# Connectors.net
KiCad netlist of a schematic drawn in Altium Designer
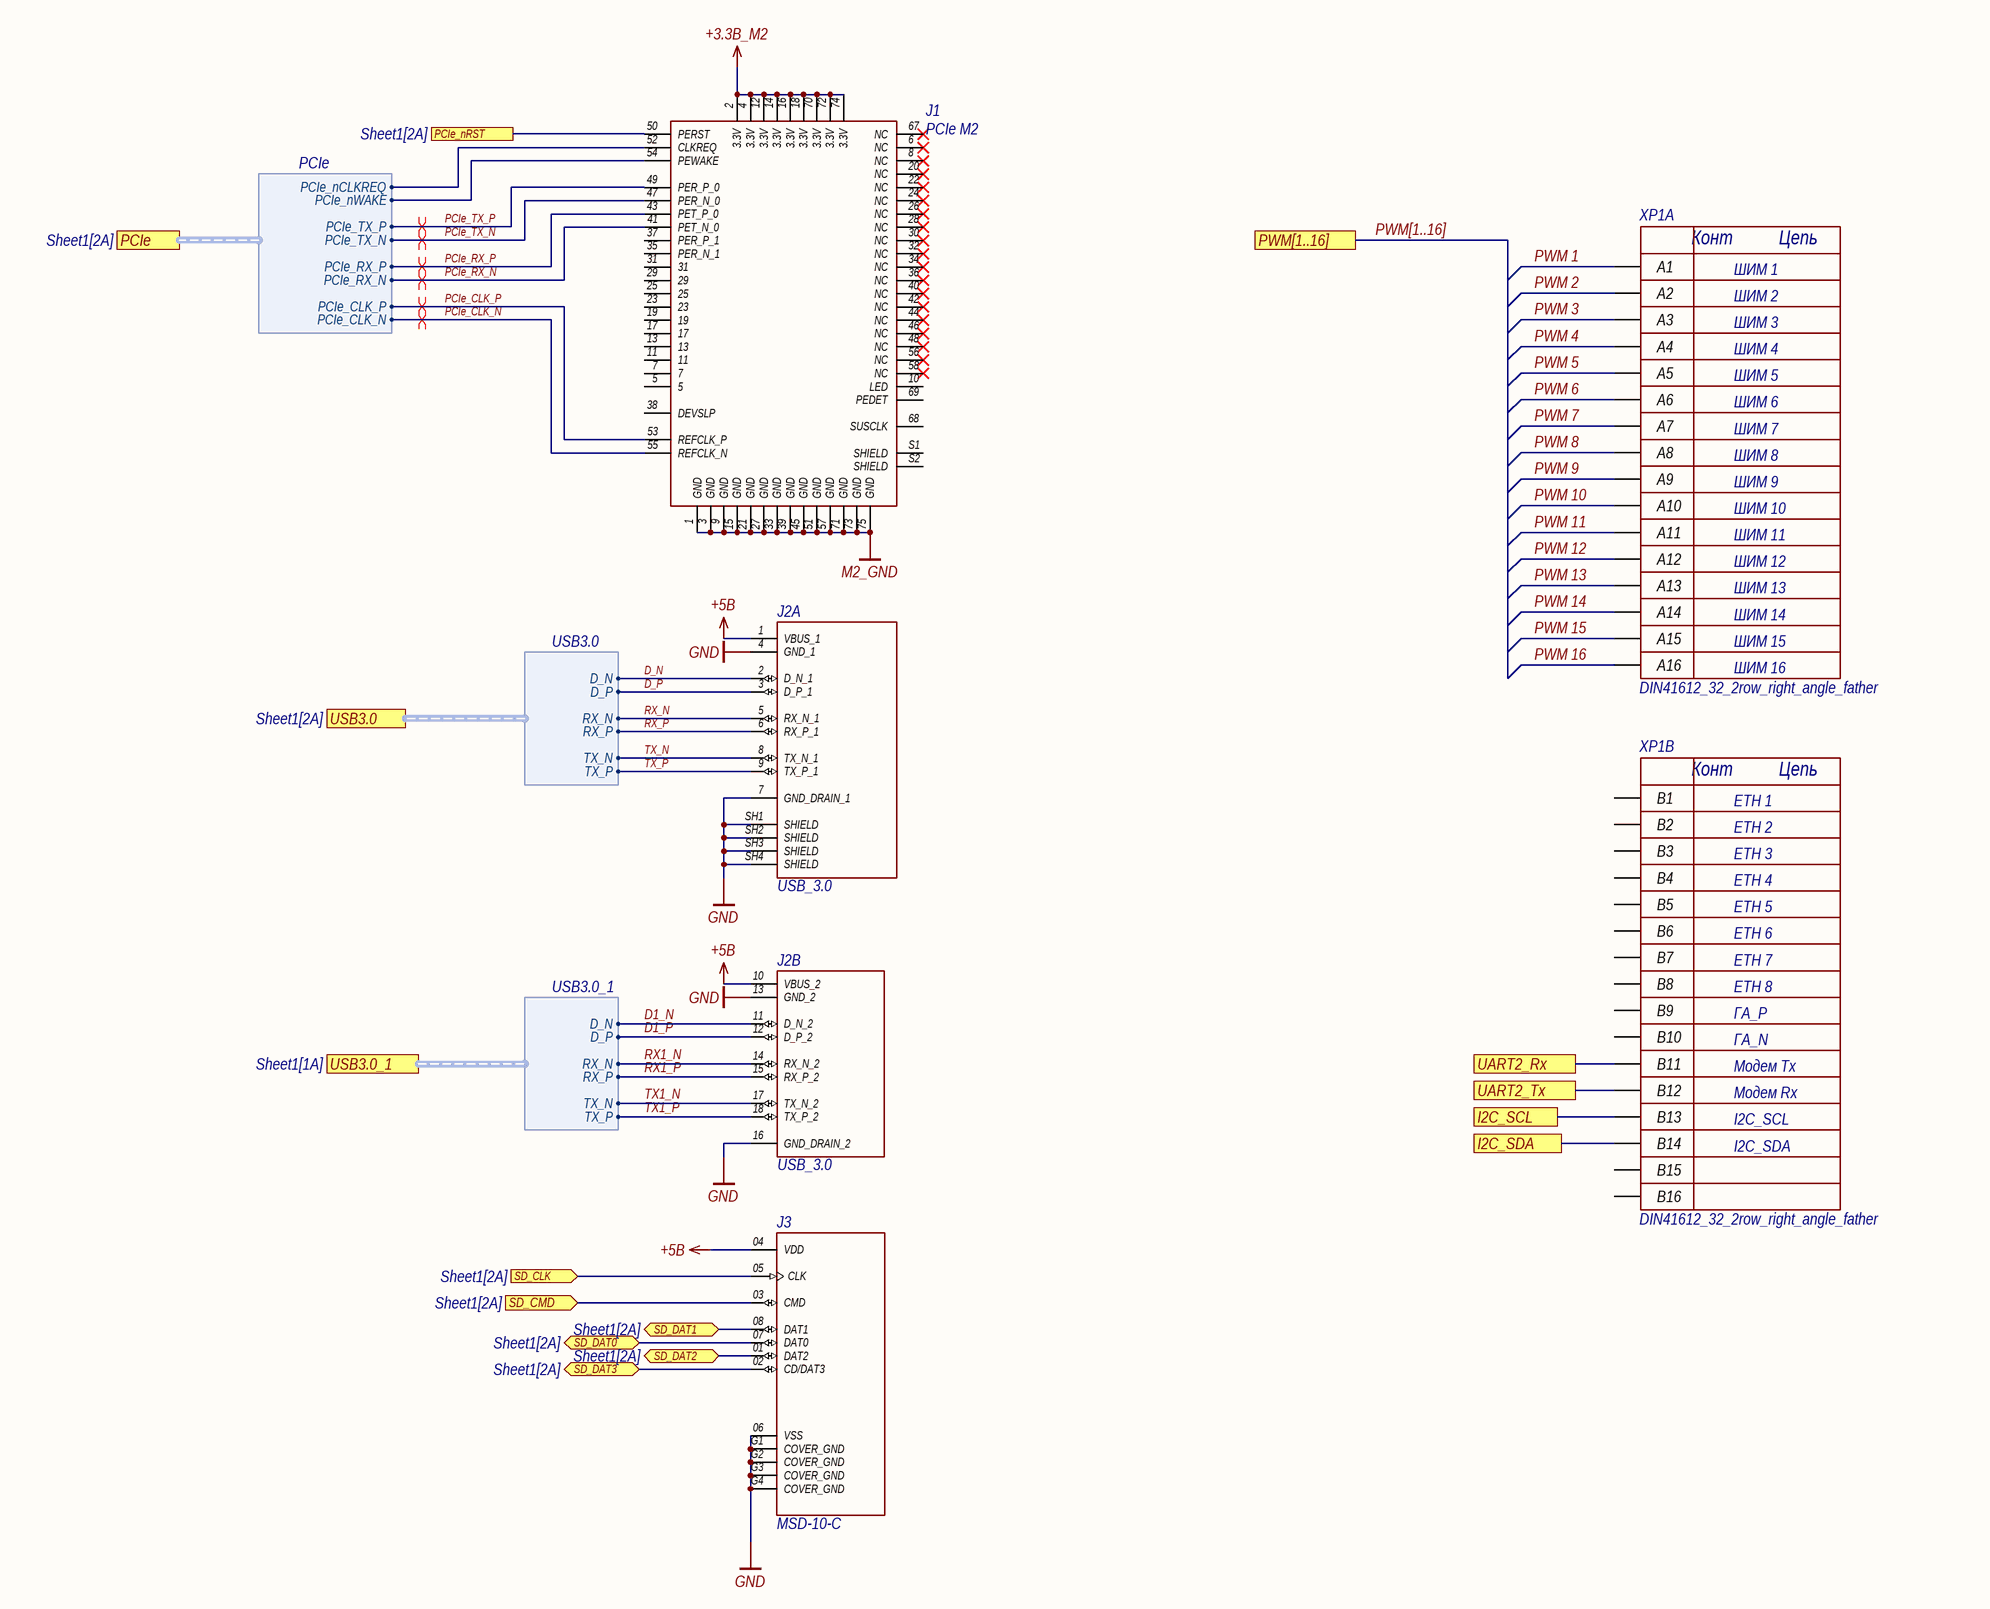
[diagram p0: Connectors.SchDoc]

(export (version "E")
  (design (tool "Eeschema 10.0.6"))
  (components
    (comp (ref "J1")
      (value "PCIe M2")
      (footprint "PCIe M2")
      (description "PCIe M.2 Connectors, Storage and Server Connector, P=0.5mm, H=3.2mm, Key M,Gold Plating")
      (fields (field (name "MF") "Amphenol") (field (name "MP") "MDT320M03001"))
      (libsource (lib "Hydrolib") (part "PCIe M2"))
    )
    (comp (ref "J2")
      (value "USB_3.0")
      (footprint "USB_3.0")
      (description "Двойной USB 3.0")
      (fields (field (name "MF") "Stewart Connector") (field (name "MP") "SS-52000-003"))
      (libsource (lib "Hydrolib") (part "USB_3.0"))
    )
    (comp (ref "J3")
      (value "MSD-10-C")
      (footprint "CUI_MSD-10-C")
      (fields (field (name "MF") "Same Sky"))
      (libsource (lib "Hydrolib") (part "MSD-10-C"))
    )
    (comp (ref "XP1")
      (value "DIN41612_32_2row_right_angle_father")
      (footprint "DIN41612_32_2row_right_angle_father")
      (libsource (lib "Hydrolib") (part "DIN41612_32_2row"))
    )
  )
  (nets
    (net (code "20") (name "+3.3В_M2") (class "Default")
      (node (ref "J1") (pin "12") (pinfunction "3.3V_12") (pintype "passive"))
      (node (ref "J1") (pin "14") (pinfunction "3.3V_14") (pintype "passive"))
      (node (ref "J1") (pin "16") (pinfunction "3.3V_16") (pintype "passive"))
      (node (ref "J1") (pin "18") (pinfunction "3.3V_18") (pintype "passive"))
      (node (ref "J1") (pin "2") (pinfunction "3.3V_2") (pintype "passive"))
      (node (ref "J1") (pin "4") (pinfunction "3.3V_4") (pintype "passive"))
      (node (ref "J1") (pin "70") (pinfunction "3.3V_70") (pintype "passive"))
      (node (ref "J1") (pin "72") (pinfunction "3.3V_72") (pintype "passive"))
      (node (ref "J1") (pin "74") (pinfunction "3.3V_74") (pintype "passive"))
    )
    (net (code "21") (name "+5В") (class "Default")
      (node (ref "J2") (pin "1") (pinfunction "VBUS_1_1") (pintype "power_in"))
      (node (ref "J2") (pin "10") (pinfunction "VBUS_2_10") (pintype "power_in"))
      (node (ref "J3") (pin "04") (pinfunction "VDD_04") (pintype "power_in"))
    )
    (net (code "22") (name "/D1_N") (class "Default")
      (node (ref "J2") (pin "11") (pinfunction "D_N_2_11") (pintype "bidirectional"))
    )
    (net (code "23") (name "/D1_P") (class "Default")
      (node (ref "J2") (pin "12") (pinfunction "D_P_2_12") (pintype "bidirectional"))
    )
    (net (code "24") (name "/D_N") (class "Default")
      (node (ref "J2") (pin "2") (pinfunction "D_N_1_2") (pintype "bidirectional"))
    )
    (net (code "25") (name "/D_P") (class "Default")
      (node (ref "J2") (pin "3") (pinfunction "D_P_1_3") (pintype "bidirectional"))
    )
    (net (code "26") (name "/I2C_SCL") (class "Default")
      (node (ref "XP1") (pin "B13") (pinfunction "B13_B13") (pintype "passive"))
    )
    (net (code "27") (name "/I2C_SDA") (class "Default")
      (node (ref "XP1") (pin "B14") (pinfunction "B14_B14") (pintype "passive"))
    )
    (net (code "28") (name "/PCIe_CLK_N") (class "Default")
      (node (ref "J1") (pin "55") (pinfunction "REFCLK_N_55") (pintype "passive"))
    )
    (net (code "29") (name "/PCIe_CLK_P") (class "Default")
      (node (ref "J1") (pin "53") (pinfunction "REFCLK_P_53") (pintype "passive"))
    )
    (net (code "30") (name "/PCIe_RX_N") (class "Default")
      (node (ref "J1") (pin "41") (pinfunction "PET_N_0_41") (pintype "passive"))
    )
    (net (code "31") (name "/PCIe_RX_P") (class "Default")
      (node (ref "J1") (pin "43") (pinfunction "PET_P_0_43") (pintype "passive"))
    )
    (net (code "32") (name "/PCIe_TX_N") (class "Default")
      (node (ref "J1") (pin "47") (pinfunction "PER_N_0_47") (pintype "passive"))
    )
    (net (code "33") (name "/PCIe_TX_P") (class "Default")
      (node (ref "J1") (pin "49") (pinfunction "PER_P_0_49") (pintype "passive"))
    )
    (net (code "34") (name "/PCIe_nCLKREQ") (class "Default")
      (node (ref "J1") (pin "52") (pinfunction "CLKREQ_52") (pintype "passive"))
    )
    (net (code "35") (name "/PCIe_nRST") (class "Default")
      (node (ref "J1") (pin "50") (pinfunction "PERST_50") (pintype "passive"))
    )
    (net (code "36") (name "/PCIe_nWAKE") (class "Default")
      (node (ref "J1") (pin "54") (pinfunction "PEWAKE_54") (pintype "passive"))
    )
    (net (code "37") (name "/PWM 1") (class "Default")
      (node (ref "XP1") (pin "A1") (pinfunction "A1_A1") (pintype "passive"))
    )
    (net (code "38") (name "/PWM 2") (class "Default")
      (node (ref "XP1") (pin "A2") (pinfunction "A2_A2") (pintype "passive"))
    )
    (net (code "39") (name "/PWM 3") (class "Default")
      (node (ref "XP1") (pin "A3") (pinfunction "A3_A3") (pintype "passive"))
    )
    (net (code "40") (name "/PWM 4") (class "Default")
      (node (ref "XP1") (pin "A4") (pinfunction "A4_A4") (pintype "passive"))
    )
    (net (code "41") (name "/PWM 5") (class "Default")
      (node (ref "XP1") (pin "A5") (pinfunction "A5_A5") (pintype "passive"))
    )
    (net (code "42") (name "/PWM 6") (class "Default")
      (node (ref "XP1") (pin "A6") (pinfunction "A6_A6") (pintype "passive"))
    )
    (net (code "43") (name "/PWM 7") (class "Default")
      (node (ref "XP1") (pin "A7") (pinfunction "A7_A7") (pintype "passive"))
    )
    (net (code "44") (name "/PWM 8") (class "Default")
      (node (ref "XP1") (pin "A8") (pinfunction "A8_A8") (pintype "passive"))
    )
    (net (code "45") (name "/PWM 9") (class "Default")
      (node (ref "XP1") (pin "A9") (pinfunction "A9_A9") (pintype "passive"))
    )
    (net (code "46") (name "/PWM 10") (class "Default")
      (node (ref "XP1") (pin "A10") (pinfunction "A10_A10") (pintype "passive"))
    )
    (net (code "47") (name "/PWM 11") (class "Default")
      (node (ref "XP1") (pin "A11") (pinfunction "A11_A11") (pintype "passive"))
    )
    (net (code "48") (name "/PWM 12") (class "Default")
      (node (ref "XP1") (pin "A12") (pinfunction "A12_A12") (pintype "passive"))
    )
    (net (code "49") (name "/PWM 13") (class "Default")
      (node (ref "XP1") (pin "A13") (pinfunction "A13_A13") (pintype "passive"))
    )
    (net (code "50") (name "/PWM 14") (class "Default")
      (node (ref "XP1") (pin "A14") (pinfunction "A14_A14") (pintype "passive"))
    )
    (net (code "51") (name "/PWM 15") (class "Default")
      (node (ref "XP1") (pin "A15") (pinfunction "A15_A15") (pintype "passive"))
    )
    (net (code "52") (name "/PWM 16") (class "Default")
      (node (ref "XP1") (pin "A16") (pinfunction "A16_A16") (pintype "passive"))
    )
    (net (code "54") (name "/RX1_N") (class "Default")
      (node (ref "J2") (pin "14") (pinfunction "RX_N_2_14") (pintype "bidirectional"))
    )
    (net (code "55") (name "/RX1_P") (class "Default")
      (node (ref "J2") (pin "15") (pinfunction "RX_P_2_15") (pintype "bidirectional"))
    )
    (net (code "56") (name "/RX_N") (class "Default")
      (node (ref "J2") (pin "5") (pinfunction "RX_N_1_5") (pintype "bidirectional"))
    )
    (net (code "57") (name "/RX_P") (class "Default")
      (node (ref "J2") (pin "6") (pinfunction "RX_P_1_6") (pintype "bidirectional"))
    )
    (net (code "58") (name "/SD_CLK") (class "Default")
      (node (ref "J3") (pin "05") (pinfunction "CLK_05") (pintype "input"))
    )
    (net (code "59") (name "/SD_CMD") (class "Default")
      (node (ref "J3") (pin "03") (pinfunction "CMD_03") (pintype "bidirectional"))
    )
    (net (code "60") (name "/SD_DAT0") (class "Default")
      (node (ref "J3") (pin "07") (pinfunction "DAT0_07") (pintype "bidirectional"))
    )
    (net (code "61") (name "/SD_DAT1") (class "Default")
      (node (ref "J3") (pin "08") (pinfunction "DAT1_08") (pintype "bidirectional"))
    )
    (net (code "62") (name "/SD_DAT2") (class "Default")
      (node (ref "J3") (pin "01") (pinfunction "DAT2_01") (pintype "bidirectional"))
    )
    (net (code "63") (name "/SD_DAT3") (class "Default")
      (node (ref "J3") (pin "02") (pinfunction "CD/DAT3_02") (pintype "bidirectional"))
    )
    (net (code "64") (name "/TX1_N") (class "Default")
      (node (ref "J2") (pin "17") (pinfunction "TX_N_2_17") (pintype "bidirectional"))
    )
    (net (code "65") (name "/TX1_P") (class "Default")
      (node (ref "J2") (pin "18") (pinfunction "TX_P_2_18") (pintype "bidirectional"))
    )
    (net (code "66") (name "/TX_N") (class "Default")
      (node (ref "J2") (pin "8") (pinfunction "TX_N_1_8") (pintype "bidirectional"))
    )
    (net (code "67") (name "/TX_P") (class "Default")
      (node (ref "J2") (pin "9") (pinfunction "TX_P_1_9") (pintype "bidirectional"))
    )
    (net (code "68") (name "/UART2_Rx") (class "Default")
      (node (ref "XP1") (pin "B11") (pinfunction "B11_B11") (pintype "passive"))
    )
    (net (code "69") (name "/UART2_Tx") (class "Default")
      (node (ref "XP1") (pin "B12") (pinfunction "B12_B12") (pintype "passive"))
    )
    (net (code "73") (name "GND") (class "Default")
      (node (ref "J2") (pin "13") (pinfunction "GND_2_13") (pintype "power_in"))
      (node (ref "J2") (pin "16") (pinfunction "GND_DRAIN_2_16") (pintype "power_in"))
      (node (ref "J2") (pin "4") (pinfunction "GND_1_4") (pintype "power_in"))
      (node (ref "J2") (pin "7") (pinfunction "GND_DRAIN_1_7") (pintype "power_in"))
      (node (ref "J2") (pin "SH1") (pinfunction "SHIELD_SH1") (pintype "passive"))
      (node (ref "J2") (pin "SH2") (pinfunction "SHIELD_SH2") (pintype "passive"))
      (node (ref "J2") (pin "SH3") (pinfunction "SHIELD_SH3") (pintype "passive"))
      (node (ref "J2") (pin "SH4") (pinfunction "SHIELD_SH4") (pintype "passive"))
      (node (ref "J3") (pin "06") (pinfunction "VSS_06") (pintype "power_in"))
      (node (ref "J3") (pin "G1") (pinfunction "COVER_GND_G1") (pintype "power_in"))
      (node (ref "J3") (pin "G2") (pinfunction "COVER_GND_G2") (pintype "power_in"))
      (node (ref "J3") (pin "G3") (pinfunction "COVER_GND_G3") (pintype "power_in"))
      (node (ref "J3") (pin "G4") (pinfunction "COVER_GND_G4") (pintype "power_in"))
    )
    (net (code "74") (name "M2_GND") (class "Default")
      (node (ref "J1") (pin "1") (pinfunction "GND_1") (pintype "passive"))
      (node (ref "J1") (pin "15") (pinfunction "GND_15") (pintype "passive"))
      (node (ref "J1") (pin "21") (pinfunction "GND_21") (pintype "passive"))
      (node (ref "J1") (pin "27") (pinfunction "GND_27") (pintype "passive"))
      (node (ref "J1") (pin "3") (pinfunction "GND_3") (pintype "passive"))
      (node (ref "J1") (pin "33") (pinfunction "GND_33") (pintype "passive"))
      (node (ref "J1") (pin "39") (pinfunction "GND_39") (pintype "passive"))
      (node (ref "J1") (pin "45") (pinfunction "GND_45") (pintype "passive"))
      (node (ref "J1") (pin "51") (pinfunction "GND_51") (pintype "passive"))
      (node (ref "J1") (pin "57") (pinfunction "GND_57") (pintype "passive"))
      (node (ref "J1") (pin "71") (pinfunction "GND_71") (pintype "passive"))
      (node (ref "J1") (pin "73") (pinfunction "GND_73") (pintype "passive"))
      (node (ref "J1") (pin "75") (pinfunction "GND_75") (pintype "passive"))
      (node (ref "J1") (pin "9") (pinfunction "GND_9") (pintype "passive"))
    )
    (net (code "75") (name "unconnected-(J1-DEVSLP-Pad38)") (class "Default")
      (node (ref "J1") (pin "38") (pinfunction "DEVSLP_38") (pintype "passive"))
    )
    (net (code "76") (name "unconnected-(J1-LED-Pad10)") (class "Default")
      (node (ref "J1") (pin "10") (pinfunction "LED_10") (pintype "passive"))
    )
    (net (code "77") (name "unconnected-(J1-NC-Pad6)") (class "Default")
      (node (ref "J1") (pin "6") (pinfunction "NC_6") (pintype "passive+no_connect"))
    )
    (net (code "78") (name "unconnected-(J1-NC-Pad8)") (class "Default")
      (node (ref "J1") (pin "8") (pinfunction "NC_8") (pintype "passive+no_connect"))
    )
    (net (code "79") (name "unconnected-(J1-NC-Pad20)") (class "Default")
      (node (ref "J1") (pin "20") (pinfunction "NC_20") (pintype "passive+no_connect"))
    )
    (net (code "80") (name "unconnected-(J1-NC-Pad22)") (class "Default")
      (node (ref "J1") (pin "22") (pinfunction "NC_22") (pintype "passive+no_connect"))
    )
    (net (code "81") (name "unconnected-(J1-NC-Pad24)") (class "Default")
      (node (ref "J1") (pin "24") (pinfunction "NC_24") (pintype "passive+no_connect"))
    )
    (net (code "82") (name "unconnected-(J1-NC-Pad26)") (class "Default")
      (node (ref "J1") (pin "26") (pinfunction "NC_26") (pintype "passive+no_connect"))
    )
    (net (code "83") (name "unconnected-(J1-NC-Pad28)") (class "Default")
      (node (ref "J1") (pin "28") (pinfunction "NC_28") (pintype "passive+no_connect"))
    )
    (net (code "84") (name "unconnected-(J1-NC-Pad30)") (class "Default")
      (node (ref "J1") (pin "30") (pinfunction "NC_30") (pintype "passive+no_connect"))
    )
    (net (code "85") (name "unconnected-(J1-NC-Pad32)") (class "Default")
      (node (ref "J1") (pin "32") (pinfunction "NC_32") (pintype "passive+no_connect"))
    )
    (net (code "86") (name "unconnected-(J1-NC-Pad34)") (class "Default")
      (node (ref "J1") (pin "34") (pinfunction "NC_34") (pintype "passive+no_connect"))
    )
    (net (code "87") (name "unconnected-(J1-NC-Pad36)") (class "Default")
      (node (ref "J1") (pin "36") (pinfunction "NC_36") (pintype "passive+no_connect"))
    )
    (net (code "88") (name "unconnected-(J1-NC-Pad40)") (class "Default")
      (node (ref "J1") (pin "40") (pinfunction "NC_40") (pintype "passive+no_connect"))
    )
    (net (code "89") (name "unconnected-(J1-NC-Pad42)") (class "Default")
      (node (ref "J1") (pin "42") (pinfunction "NC_42") (pintype "passive+no_connect"))
    )
    (net (code "90") (name "unconnected-(J1-NC-Pad44)") (class "Default")
      (node (ref "J1") (pin "44") (pinfunction "NC_44") (pintype "passive+no_connect"))
    )
    (net (code "91") (name "unconnected-(J1-NC-Pad46)") (class "Default")
      (node (ref "J1") (pin "46") (pinfunction "NC_46") (pintype "passive+no_connect"))
    )
    (net (code "92") (name "unconnected-(J1-NC-Pad48)") (class "Default")
      (node (ref "J1") (pin "48") (pinfunction "NC_48") (pintype "passive+no_connect"))
    )
    (net (code "93") (name "unconnected-(J1-NC-Pad56)") (class "Default")
      (node (ref "J1") (pin "56") (pinfunction "NC_56") (pintype "passive+no_connect"))
    )
    (net (code "94") (name "unconnected-(J1-NC-Pad58)") (class "Default")
      (node (ref "J1") (pin "58") (pinfunction "NC_58") (pintype "passive+no_connect"))
    )
    (net (code "95") (name "unconnected-(J1-NC-Pad67)") (class "Default")
      (node (ref "J1") (pin "67") (pinfunction "NC_67") (pintype "passive+no_connect"))
    )
    (net (code "96") (name "unconnected-(J1-PEDET-Pad69)") (class "Default")
      (node (ref "J1") (pin "69") (pinfunction "PEDET_69") (pintype "passive"))
    )
    (net (code "97") (name "unconnected-(J1-PER_N_1-Pad35)") (class "Default")
      (node (ref "J1") (pin "35") (pinfunction "PER_N_1_35") (pintype "passive"))
    )
    (net (code "98") (name "unconnected-(J1-PER_P_1-Pad37)") (class "Default")
      (node (ref "J1") (pin "37") (pinfunction "PER_P_1_37") (pintype "passive"))
    )
    (net (code "99") (name "unconnected-(J1-Pad5)") (class "Default")
      (node (ref "J1") (pin "5") (pinfunction "5_5") (pintype "passive"))
    )
    (net (code "100") (name "unconnected-(J1-Pad7)") (class "Default")
      (node (ref "J1") (pin "7") (pinfunction "7_7") (pintype "passive"))
    )
    (net (code "101") (name "unconnected-(J1-Pad11)") (class "Default")
      (node (ref "J1") (pin "11") (pinfunction "11_11") (pintype "passive"))
    )
    (net (code "102") (name "unconnected-(J1-Pad13)") (class "Default")
      (node (ref "J1") (pin "13") (pinfunction "13_13") (pintype "passive"))
    )
    (net (code "103") (name "unconnected-(J1-Pad17)") (class "Default")
      (node (ref "J1") (pin "17") (pinfunction "17_17") (pintype "passive"))
    )
    (net (code "104") (name "unconnected-(J1-Pad19)") (class "Default")
      (node (ref "J1") (pin "19") (pinfunction "19_19") (pintype "passive"))
    )
    (net (code "105") (name "unconnected-(J1-Pad23)") (class "Default")
      (node (ref "J1") (pin "23") (pinfunction "23_23") (pintype "passive"))
    )
    (net (code "106") (name "unconnected-(J1-Pad25)") (class "Default")
      (node (ref "J1") (pin "25") (pinfunction "25_25") (pintype "passive"))
    )
    (net (code "107") (name "unconnected-(J1-Pad29)") (class "Default")
      (node (ref "J1") (pin "29") (pinfunction "29_29") (pintype "passive"))
    )
    (net (code "108") (name "unconnected-(J1-Pad31)") (class "Default")
      (node (ref "J1") (pin "31") (pinfunction "31_31") (pintype "passive"))
    )
    (net (code "109") (name "unconnected-(J1-SHIELD-PadS1)") (class "Default")
      (node (ref "J1") (pin "S1") (pinfunction "SHIELD_S1") (pintype "passive"))
    )
    (net (code "110") (name "unconnected-(J1-SHIELD-PadS2)") (class "Default")
      (node (ref "J1") (pin "S2") (pinfunction "SHIELD_S2") (pintype "passive"))
    )
    (net (code "111") (name "unconnected-(J1-SUSCLK-Pad68)") (class "Default")
      (node (ref "J1") (pin "68") (pinfunction "SUSCLK_68") (pintype "passive"))
    )
    (net (code "112") (name "unconnected-(XP1-PadB1)") (class "Default")
      (node (ref "XP1") (pin "B1") (pinfunction "B1_B1") (pintype "passive"))
    )
    (net (code "113") (name "unconnected-(XP1-PadB2)") (class "Default")
      (node (ref "XP1") (pin "B2") (pinfunction "B2_B2") (pintype "passive"))
    )
    (net (code "114") (name "unconnected-(XP1-PadB3)") (class "Default")
      (node (ref "XP1") (pin "B3") (pinfunction "B3_B3") (pintype "passive"))
    )
    (net (code "115") (name "unconnected-(XP1-PadB4)") (class "Default")
      (node (ref "XP1") (pin "B4") (pinfunction "B4_B4") (pintype "passive"))
    )
    (net (code "116") (name "unconnected-(XP1-PadB5)") (class "Default")
      (node (ref "XP1") (pin "B5") (pinfunction "B5_B5") (pintype "passive"))
    )
    (net (code "117") (name "unconnected-(XP1-PadB6)") (class "Default")
      (node (ref "XP1") (pin "B6") (pinfunction "B6_B6") (pintype "passive"))
    )
    (net (code "118") (name "unconnected-(XP1-PadB7)") (class "Default")
      (node (ref "XP1") (pin "B7") (pinfunction "B7_B7") (pintype "passive"))
    )
    (net (code "119") (name "unconnected-(XP1-PadB8)") (class "Default")
      (node (ref "XP1") (pin "B8") (pinfunction "B8_B8") (pintype "passive"))
    )
    (net (code "120") (name "unconnected-(XP1-PadB9)") (class "Default")
      (node (ref "XP1") (pin "B9") (pinfunction "B9_B9") (pintype "passive"))
    )
    (net (code "121") (name "unconnected-(XP1-PadB10)") (class "Default")
      (node (ref "XP1") (pin "B10") (pinfunction "B10_B10") (pintype "passive"))
    )
    (net (code "122") (name "unconnected-(XP1-PadB15)") (class "Default")
      (node (ref "XP1") (pin "B15") (pinfunction "B15_B15") (pintype "passive"))
    )
    (net (code "123") (name "unconnected-(XP1-PadB16)") (class "Default")
      (node (ref "XP1") (pin "B16") (pinfunction "B16_B16") (pintype "passive"))
    )
  )
)
